# LED_Test_PIO_2.net
KiCad netlist of a schematic drawn in EAGLE
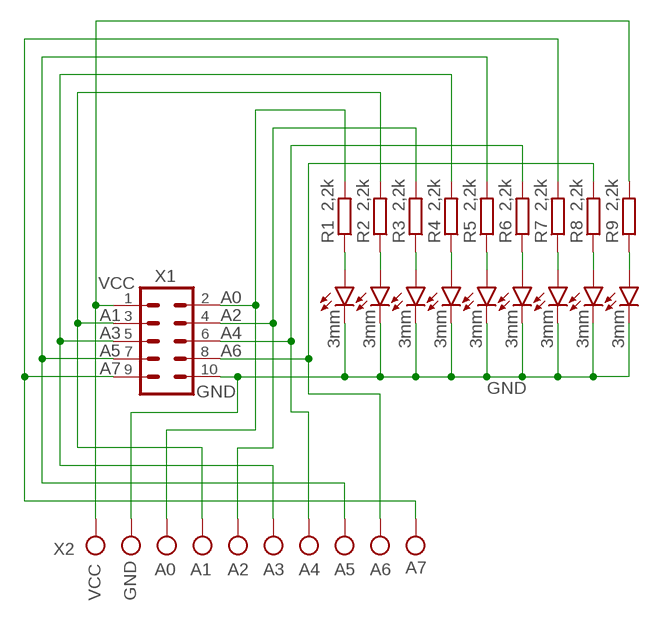
[diagram p0: schematic, sheet 1]

(export (version "E")
  (design (tool "Eeschema 10.0.6"))
  (components
    (comp (ref "LED1")
      (value "3mm")
      (footprint "eagle-import:LED3MM")
      (libsource (lib "eagle-import") (part "LED3MM"))
    )
    (comp (ref "LED2")
      (value "3mm")
      (footprint "eagle-import:LED3MM")
      (libsource (lib "eagle-import") (part "LED3MM"))
    )
    (comp (ref "LED3")
      (value "3mm")
      (footprint "eagle-import:LED3MM")
      (libsource (lib "eagle-import") (part "LED3MM"))
    )
    (comp (ref "LED4")
      (value "3mm")
      (footprint "eagle-import:LED3MM")
      (libsource (lib "eagle-import") (part "LED3MM"))
    )
    (comp (ref "LED5")
      (value "3mm")
      (footprint "eagle-import:LED3MM")
      (libsource (lib "eagle-import") (part "LED3MM"))
    )
    (comp (ref "LED6")
      (value "3mm")
      (footprint "eagle-import:LED3MM")
      (libsource (lib "eagle-import") (part "LED3MM"))
    )
    (comp (ref "LED7")
      (value "3mm")
      (footprint "eagle-import:LED3MM")
      (libsource (lib "eagle-import") (part "LED3MM"))
    )
    (comp (ref "LED8")
      (value "3mm")
      (footprint "eagle-import:LED3MM")
      (libsource (lib "eagle-import") (part "LED3MM"))
    )
    (comp (ref "LED9")
      (value "3mm")
      (footprint "eagle-import:LED3MM")
      (libsource (lib "eagle-import") (part "LED3MM"))
    )
    (comp (ref "R1")
      (value "2,2k")
      (footprint "eagle-import:0207_10")
      (libsource (lib "eagle-import") (part "R-EU_0207/10"))
    )
    (comp (ref "R2")
      (value "2,2k")
      (footprint "eagle-import:0207_10")
      (libsource (lib "eagle-import") (part "R-EU_0207/10"))
    )
    (comp (ref "R3")
      (value "2,2k")
      (footprint "eagle-import:0207_10")
      (libsource (lib "eagle-import") (part "R-EU_0207/10"))
    )
    (comp (ref "R4")
      (value "2,2k")
      (footprint "eagle-import:0207_10")
      (libsource (lib "eagle-import") (part "R-EU_0207/10"))
    )
    (comp (ref "R5")
      (value "2,2k")
      (footprint "eagle-import:0207_10")
      (libsource (lib "eagle-import") (part "R-EU_0207/10"))
    )
    (comp (ref "R6")
      (value "2,2k")
      (footprint "eagle-import:0207_10")
      (libsource (lib "eagle-import") (part "R-EU_0207/10"))
    )
    (comp (ref "R7")
      (value "2,2k")
      (footprint "eagle-import:0207_10")
      (libsource (lib "eagle-import") (part "R-EU_0207/10"))
    )
    (comp (ref "R8")
      (value "2,2k")
      (footprint "eagle-import:0207_10")
      (libsource (lib "eagle-import") (part "R-EU_0207/10"))
    )
    (comp (ref "R9")
      (value "2,2k")
      (footprint "eagle-import:0207_10")
      (libsource (lib "eagle-import") (part "R-EU_0207/10"))
    )
    (comp (ref "SV1")
      (value "X1")
      (footprint "eagle-import:ML10")
      (libsource (lib "eagle-import") (part "ML10"))
    )
    (comp (ref "X1")
      (value "X2")
      (footprint "eagle-import:W237-102")
      (fields (field (name "MPN") "237-102"))
      (libsource (lib "eagle-import") (part "W237-102"))
    )
    (comp (ref "X2")
      (value "X2")
      (footprint "eagle-import:W237-102")
      (fields (field (name "MPN") "237-102"))
      (libsource (lib "eagle-import") (part "W237-102"))
    )
    (comp (ref "X3")
      (value "X2")
      (footprint "eagle-import:W237-102")
      (fields (field (name "MPN") "237-102"))
      (libsource (lib "eagle-import") (part "W237-102"))
    )
    (comp (ref "X4")
      (value "X2")
      (footprint "eagle-import:W237-102")
      (fields (field (name "MPN") "237-102"))
      (libsource (lib "eagle-import") (part "W237-102"))
    )
    (comp (ref "X5")
      (value "X2")
      (footprint "eagle-import:W237-102")
      (fields (field (name "MPN") "237-102"))
      (libsource (lib "eagle-import") (part "W237-102"))
    )
  )
  (nets
    (net (code "1") (name "/A0") (class "Default")
      (node (ref "R1") (pin "2") (pinfunction "2_2") (pintype "passive"))
      (node (ref "SV1") (pin "2") (pinfunction "2_2") (pintype "passive"))
      (node (ref "X2") (pin "1") (pinfunction "KL_1") (pintype "passive"))
    )
    (net (code "2") (name "/A1") (class "Default")
      (node (ref "R2") (pin "2") (pinfunction "2_2") (pintype "passive"))
      (node (ref "SV1") (pin "3") (pinfunction "3_3") (pintype "passive"))
      (node (ref "X2") (pin "2") (pinfunction "KL_2") (pintype "passive"))
    )
    (net (code "3") (name "/A2") (class "Default")
      (node (ref "R3") (pin "2") (pinfunction "2_2") (pintype "passive"))
      (node (ref "SV1") (pin "4") (pinfunction "4_4") (pintype "passive"))
      (node (ref "X3") (pin "1") (pinfunction "KL_1") (pintype "passive"))
    )
    (net (code "4") (name "/A3") (class "Default")
      (node (ref "R4") (pin "2") (pinfunction "2_2") (pintype "passive"))
      (node (ref "SV1") (pin "5") (pinfunction "5_5") (pintype "passive"))
      (node (ref "X3") (pin "2") (pinfunction "KL_2") (pintype "passive"))
    )
    (net (code "5") (name "/A4") (class "Default")
      (node (ref "R6") (pin "2") (pinfunction "2_2") (pintype "passive"))
      (node (ref "SV1") (pin "6") (pinfunction "6_6") (pintype "passive"))
      (node (ref "X4") (pin "1") (pinfunction "KL_1") (pintype "passive"))
    )
    (net (code "6") (name "/A5") (class "Default")
      (node (ref "R5") (pin "2") (pinfunction "2_2") (pintype "passive"))
      (node (ref "SV1") (pin "7") (pinfunction "7_7") (pintype "passive"))
      (node (ref "X4") (pin "2") (pinfunction "KL_2") (pintype "passive"))
    )
    (net (code "7") (name "/A6") (class "Default")
      (node (ref "R8") (pin "2") (pinfunction "2_2") (pintype "passive"))
      (node (ref "SV1") (pin "8") (pinfunction "8_8") (pintype "passive"))
      (node (ref "X5") (pin "1") (pinfunction "KL_1") (pintype "passive"))
    )
    (net (code "8") (name "/A7") (class "Default")
      (node (ref "R7") (pin "2") (pinfunction "2_2") (pintype "passive"))
      (node (ref "SV1") (pin "9") (pinfunction "9_9") (pintype "passive"))
      (node (ref "X5") (pin "2") (pinfunction "KL_2") (pintype "passive"))
    )
    (net (code "9") (name "/GND") (class "Default")
      (node (ref "LED1") (pin "K") (pinfunction "C_K") (pintype "passive"))
      (node (ref "LED2") (pin "K") (pinfunction "C_K") (pintype "passive"))
      (node (ref "LED3") (pin "K") (pinfunction "C_K") (pintype "passive"))
      (node (ref "LED4") (pin "K") (pinfunction "C_K") (pintype "passive"))
      (node (ref "LED5") (pin "K") (pinfunction "C_K") (pintype "passive"))
      (node (ref "LED6") (pin "K") (pinfunction "C_K") (pintype "passive"))
      (node (ref "LED7") (pin "K") (pinfunction "C_K") (pintype "passive"))
      (node (ref "LED8") (pin "K") (pinfunction "C_K") (pintype "passive"))
      (node (ref "LED9") (pin "K") (pinfunction "C_K") (pintype "passive"))
      (node (ref "SV1") (pin "10") (pinfunction "10_10") (pintype "passive"))
      (node (ref "X1") (pin "2") (pinfunction "KL_2") (pintype "passive"))
    )
    (net (code "10") (name "/VCC") (class "Default")
      (node (ref "R9") (pin "2") (pinfunction "2_2") (pintype "passive"))
      (node (ref "SV1") (pin "1") (pinfunction "1_1") (pintype "passive"))
      (node (ref "X1") (pin "1") (pinfunction "KL_1") (pintype "passive"))
    )
    (net (code "11") (name "Net-(LED1-PadA)") (class "Default")
      (node (ref "LED1") (pin "A") (pinfunction "A_A") (pintype "passive"))
      (node (ref "R1") (pin "1") (pinfunction "1_1") (pintype "passive"))
    )
    (net (code "12") (name "Net-(LED2-PadA)") (class "Default")
      (node (ref "LED2") (pin "A") (pinfunction "A_A") (pintype "passive"))
      (node (ref "R2") (pin "1") (pinfunction "1_1") (pintype "passive"))
    )
    (net (code "13") (name "Net-(LED3-PadA)") (class "Default")
      (node (ref "LED3") (pin "A") (pinfunction "A_A") (pintype "passive"))
      (node (ref "R3") (pin "1") (pinfunction "1_1") (pintype "passive"))
    )
    (net (code "14") (name "Net-(LED4-PadA)") (class "Default")
      (node (ref "LED4") (pin "A") (pinfunction "A_A") (pintype "passive"))
      (node (ref "R4") (pin "1") (pinfunction "1_1") (pintype "passive"))
    )
    (net (code "15") (name "Net-(LED5-PadA)") (class "Default")
      (node (ref "LED5") (pin "A") (pinfunction "A_A") (pintype "passive"))
      (node (ref "R5") (pin "1") (pinfunction "1_1") (pintype "passive"))
    )
    (net (code "16") (name "Net-(LED6-PadA)") (class "Default")
      (node (ref "LED6") (pin "A") (pinfunction "A_A") (pintype "passive"))
      (node (ref "R6") (pin "1") (pinfunction "1_1") (pintype "passive"))
    )
    (net (code "17") (name "Net-(LED7-PadA)") (class "Default")
      (node (ref "LED7") (pin "A") (pinfunction "A_A") (pintype "passive"))
      (node (ref "R7") (pin "1") (pinfunction "1_1") (pintype "passive"))
    )
    (net (code "18") (name "Net-(LED8-PadA)") (class "Default")
      (node (ref "LED8") (pin "A") (pinfunction "A_A") (pintype "passive"))
      (node (ref "R8") (pin "1") (pinfunction "1_1") (pintype "passive"))
    )
    (net (code "19") (name "Net-(LED9-PadA)") (class "Default")
      (node (ref "LED9") (pin "A") (pinfunction "A_A") (pintype "passive"))
      (node (ref "R9") (pin "1") (pinfunction "1_1") (pintype "passive"))
    )
  )
)
